# Power_Supply.net
KiCad netlist of a schematic drawn in Altium Designer
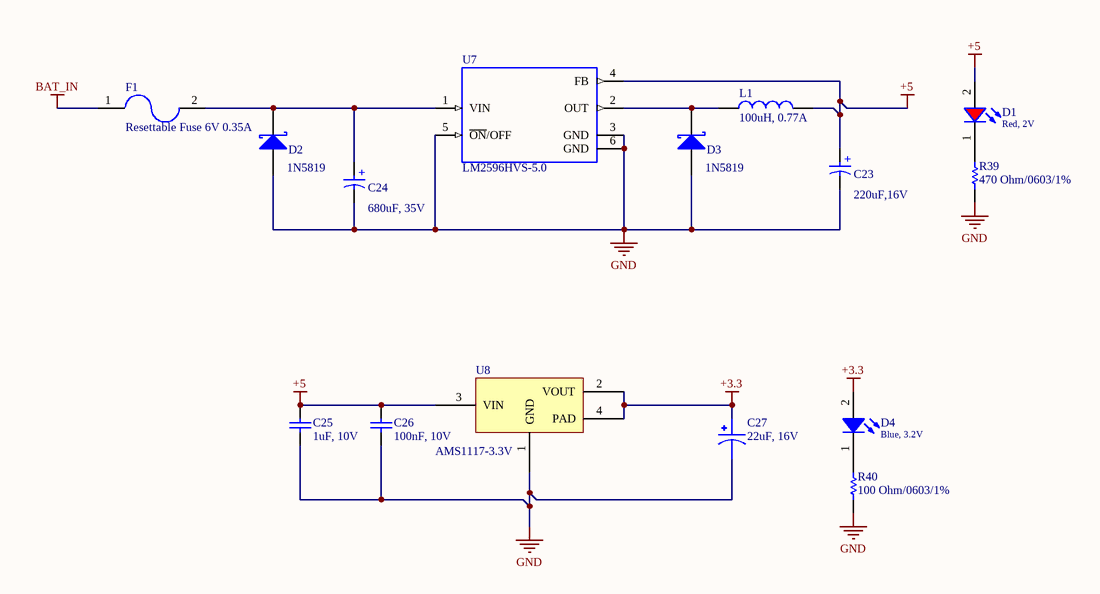
[diagram p0: Power_Supply.SchDoc]

(export (version "E")
  (design (tool "Eeschema 10.0.6"))
  (components
    (comp (ref "C23")
      (value "220uF,16V")
      (footprint "WCAP-ASLI_D6.3H7.7")
      (description "WCAP-ASLI Aluminum Electrolytic Capacitor, V-Chip, D6.3 x H7.7mm, 220uF, 16V")
      (fields
        (field (name "MANUFACTURER PART NUMBER") "865080345012")
        (field (name "MANUFACTURER") "Wurth Elektronik")
      )
      (libsource (lib "Altium_WCAP-ASLI (rev22d)") (part "865080345012"))
    )
    (comp (ref "C24")
      (value "680uF, 35V")
      (footprint "WCAP-ASLI_D12.5H14")
      (description "WCAP-ASLI Aluminum Electrolytic Capacitor, V-Chip, D12.5 x H14mm, 680uF, 35V")
      (fields
        (field (name "MANUFACTURER PART NUMBER") "865080562017")
        (field (name "MANUFACTURER") "Wurth Elektronik")
      )
      (libsource (lib "Altium_WCAP-ASLI (rev22d)") (part "865080562017"))
    )
    (comp (ref "C25")
      (value "1uF, 10V")
      (footprint "WCAP-CSGP_0603_H=0.8mm_Reflow")
      (description "WCAP-CSGP Multilayer Ceramic Chip Capacitor, General Purpose, size 0603, X5R, 1uF, 10V")
      (fields
        (field (name "MANUFACTURER PART NUMBER") "885012106010")
        (field (name "MANUFACTURER") "Wurth Elektronik")
      )
      (libsource (lib "Altium_WCAP-CSGP (rev20a)") (part "885012106010"))
    )
    (comp (ref "C26")
      (value "100nF, 10V")
      (footprint "WCAP-CSGP_0603_H=0.8mm_Reflow")
      (description "WCAP-CSGP Multilayer Ceramic Chip Capacitor, General Purpose, size 0603, X7R, 100nF, 10V")
      (fields
        (field (name "MANUFACTURER PART NUMBER") "885012206020")
        (field (name "MANUFACTURER") "Wurth Elektronik")
      )
      (libsource (lib "Altium_WCAP-CSGP (rev20a)") (part "885012206020"))
    )
    (comp (ref "C27")
      (value "22uF, 16V")
      (footprint "C2312")
      (description "Code 226 10%, 2312 (6032 Metric)")
      (fields (field (name "MF") "AVX") (field (name "MP") "TAJC226K016RNJ"))
      (libsource (lib "Giang's Libs") (part "Tantalum Capacitor"))
    )
    (comp (ref "D1")
      (value "Red, 2V")
      (footprint "WL-SMCW_0603 dome")
      (description "WL-SMCW SMT Mono-color Chip LED Waterclear, size 0603 dome, Red, 2V, 60deg")
      (fields (field (name "PART NUMBER") "150060RS86000") (field (name "PUBLISHER") "Wurth Elektronik"))
      (libsource (lib "Altium_WL-SMCW (rev20a)") (part "150060RS86000"))
    )
    (comp (ref "D2")
      (value "1N5819")
      (footprint "SS34")
      (description "Schottky Diode")
      (fields (field (name "Comment") "D Schottky") (field (name "PUBLISHER") "Altium Limited"))
      (libsource (lib "PIF_Library") (part "D Schottky"))
    )
    (comp (ref "D3")
      (value "1N5819")
      (footprint "SS34")
      (description "Schottky Diode")
      (fields (field (name "Comment") "D Schottky") (field (name "PUBLISHER") "Altium Limited"))
      (libsource (lib "PIF_Library") (part "D Schottky"))
    )
    (comp (ref "D4")
      (value "Blue, 3.2V")
      (footprint "WL-SMCW_0603_H=0.7mm")
      (description "WL-SMCW SMT Mono-color Chip LED Waterclear, size 0603, Blue, 3.2V, 140deg")
      (fields (field (name "PART NUMBER") "150060BS75000") (field (name "PUBLISHER") "Wurth Elektronik"))
      (libsource (lib "Altium_WL-SMCW (rev20a)") (part "150060BS75000"))
    )
    (comp (ref "F1")
      (value "Resettable Fuse 6V 0.35A")
      (footprint "FUSE1206")
      (description "Polymeric PTC Resettable Fuse 6V 350mA Ih Surface Mount 1206 _3216 Metric_, Concave")
      (fields (field (name "MF") "Littelfuse Inc.") (field (name "MP") "1206L035YR"))
      (libsource (lib "Giang's Libs") (part "RESETTABLE FUSE 1206"))
    )
    (comp (ref "L1")
      (value "100uH, 0.77A")
      (footprint "WE-PD2A_7850")
      (description "WE-PD2A SMT Power Inductor, size 7850, 100uH, 0.77A")
      (fields
        (field (name "MANUFACTURER PART NUMBER") "78477520")
        (field (name "MANUFACTURER") "Wurth Elektronik")
      )
      (libsource (lib "Altium_WE-PD2A (rev20a)") (part "78477520"))
    )
    (comp (ref "R39")
      (value "470 Ohm/0603/1%")
      (footprint "R0603")
      (description "Code 471, 1/10W")
      (fields (field (name "Comment") "Resistor 470 Ohm 0603 1%"))
      (libsource (lib "Giang_Resistor") (part "Resistor 470 Ohm 0603 1%"))
    )
    (comp (ref "R40")
      (value "100 Ohm/0603/1%")
      (footprint "R0603")
      (description "Code 1000, 1/10W")
      (fields (field (name "Comment") "Resistor 100 Ohm 0603 1%"))
      (libsource (lib "Giang_Resistor") (part "Resistor 100 Ohm 0603 1%"))
    )
    (comp (ref "U7")
      (value "LM2596HVS-5.0")
      (footprint "TO-263-5")
      (description "Simple Switcher Power Converter 150-kHz 4V to 60V, 3A Step-Down Voltage Regulator")
      (fields (field (name "MF") "Texas Instruments") (field (name "MP") "LM2576HVS-5.0/NOPB"))
      (libsource (lib "Giang's Libs") (part "LM2596"))
    )
    (comp (ref "U8")
      (value "AMS1117-3.3V")
      (footprint "SOT230P700X180-4N")
      (libsource (lib "MiclsLib") (part "AMS1117-3.3V"))
    )
  )
  (nets
    (net (code "1") (name "+3.3") (class "Default")
      (node (ref "C27") (pin "1") (pinfunction "1_1") (pintype "passive"))
      (node (ref "D4") (pin "2") (pinfunction "A_2") (pintype "passive"))
      (node (ref "U8") (pin "2") (pinfunction "VOUT_2") (pintype "passive"))
      (node (ref "U8") (pin "4") (pinfunction "PAD_4") (pintype "passive"))
    )
    (net (code "2") (name "+5") (class "Default")
      (node (ref "C23") (pin "1") (pinfunction "P_1") (pintype "passive"))
      (node (ref "C25") (pin "2") (pinfunction "2_2") (pintype "passive"))
      (node (ref "C26") (pin "2") (pinfunction "2_2") (pintype "passive"))
      (node (ref "D1") (pin "2") (pinfunction "A_2") (pintype "passive"))
      (node (ref "L1") (pin "2") (pinfunction "2_2") (pintype "passive"))
      (node (ref "U7") (pin "4") (pinfunction "FB_4") (pintype "output"))
      (node (ref "U8") (pin "3") (pinfunction "VIN_3") (pintype "passive"))
    )
    (net (code "3") (name "BAT_IN") (class "Default")
      (node (ref "F1") (pin "1") (pinfunction "1_1") (pintype "passive"))
    )
    (net (code "4") (name "GND") (class "Default")
      (node (ref "C23") (pin "2") (pinfunction "N_2") (pintype "passive"))
      (node (ref "C24") (pin "2") (pinfunction "N_2") (pintype "passive"))
      (node (ref "C25") (pin "1") (pinfunction "1_1") (pintype "passive"))
      (node (ref "C26") (pin "1") (pinfunction "1_1") (pintype "passive"))
      (node (ref "C27") (pin "2") (pinfunction "2_2") (pintype "passive"))
      (node (ref "D2") (pin "1") (pinfunction "A_1") (pintype "passive"))
      (node (ref "D3") (pin "1") (pinfunction "A_1") (pintype "passive"))
      (node (ref "R39") (pin "1") (pinfunction "1_1") (pintype "passive"))
      (node (ref "R40") (pin "1") (pinfunction "1_1") (pintype "passive"))
      (node (ref "U7") (pin "3") (pinfunction "GND_3") (pintype "power_in"))
      (node (ref "U7") (pin "5") (pinfunction "~{ON}/OFF_5") (pintype "input"))
      (node (ref "U7") (pin "6") (pinfunction "GND_6") (pintype "power_in"))
      (node (ref "U8") (pin "1") (pinfunction "GND_1") (pintype "passive"))
    )
    (net (code "5") (name "Net-(C24-P)") (class "Default")
      (node (ref "C24") (pin "1") (pinfunction "P_1") (pintype "passive"))
      (node (ref "D2") (pin "2") (pinfunction "K_2") (pintype "passive"))
      (node (ref "F1") (pin "2") (pinfunction "2_2") (pintype "passive"))
      (node (ref "U7") (pin "1") (pinfunction "VIN_1") (pintype "input"))
    )
    (net (code "6") (name "Net-(D1-K)") (class "Default")
      (node (ref "D1") (pin "1") (pinfunction "K_1") (pintype "passive"))
      (node (ref "R39") (pin "2") (pinfunction "2_2") (pintype "passive"))
    )
    (net (code "7") (name "Net-(D3-K)") (class "Default")
      (node (ref "D3") (pin "2") (pinfunction "K_2") (pintype "passive"))
      (node (ref "L1") (pin "1") (pinfunction "1_1") (pintype "passive"))
      (node (ref "U7") (pin "2") (pinfunction "OUT_2") (pintype "output"))
    )
    (net (code "8") (name "Net-(D4-K)") (class "Default")
      (node (ref "D4") (pin "1") (pinfunction "K_1") (pintype "passive"))
      (node (ref "R40") (pin "2") (pinfunction "2_2") (pintype "passive"))
    )
  )
)
